# ESP07_Breakout.net
KiCad netlist of a schematic drawn in EAGLE
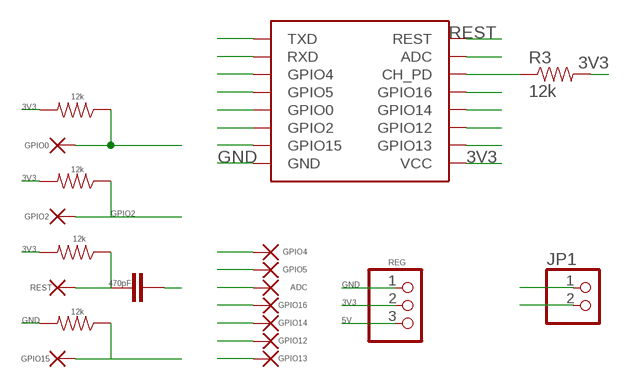
[diagram p0: schematic, sheet 1]

(export (version "E")
  (design (tool "Eeschema 10.0.6"))
  (components
    (comp (ref "ADC")
      (value "1,6/0,8")
      (footprint "eagle-import:1,6_0,8")
      (libsource (lib "eagle-import") (part "1,6/0,8"))
    )
    (comp (ref "C1")
      (value "470pF")
      (footprint "eagle-import:0603-CAP")
      (libsource (lib "eagle-import") (part "CAP0603-CAP"))
    )
    (comp (ref "GPIO0")
      (value "1,6/0,8")
      (footprint "eagle-import:1,6_0,8")
      (libsource (lib "eagle-import") (part "1,6/0,8"))
    )
    (comp (ref "GPIO2")
      (value "1,6/0,8")
      (footprint "eagle-import:1,6_0,8")
      (libsource (lib "eagle-import") (part "1,6/0,8"))
    )
    (comp (ref "GPIO4")
      (value "1,6/0,8")
      (footprint "eagle-import:1,6_0,8")
      (libsource (lib "eagle-import") (part "1,6/0,8"))
    )
    (comp (ref "GPIO5")
      (value "1,6/0,8")
      (footprint "eagle-import:1,6_0,8")
      (libsource (lib "eagle-import") (part "1,6/0,8"))
    )
    (comp (ref "GPIO12")
      (value "1,6/0,8")
      (footprint "eagle-import:1,6_0,8")
      (libsource (lib "eagle-import") (part "1,6/0,8"))
    )
    (comp (ref "GPIO13")
      (value "1,6/0,8")
      (footprint "eagle-import:1,6_0,8")
      (libsource (lib "eagle-import") (part "1,6/0,8"))
    )
    (comp (ref "GPIO14")
      (value "1,6/0,8")
      (footprint "eagle-import:1,6_0,8")
      (libsource (lib "eagle-import") (part "1,6/0,8"))
    )
    (comp (ref "GPIO15")
      (value "1,6/0,8")
      (footprint "eagle-import:1,6_0,8")
      (libsource (lib "eagle-import") (part "1,6/0,8"))
    )
    (comp (ref "GPIO16")
      (value "1,6/0,8")
      (footprint "eagle-import:1,6_0,8")
      (libsource (lib "eagle-import") (part "1,6/0,8"))
    )
    (comp (ref "JP1")
      (value "PINHD-1X2/90")
      (footprint "eagle-import:1X02_90")
      (libsource (lib "eagle-import") (part "PINHD-1X2/90"))
    )
    (comp (ref "R1")
      (value "12k")
      (footprint "eagle-import:0603-RES")
      (libsource (lib "eagle-import") (part "RESISTOR0603-RES"))
    )
    (comp (ref "R2")
      (value "12k")
      (footprint "eagle-import:0603-RES")
      (libsource (lib "eagle-import") (part "RESISTOR0603-RES"))
    )
    (comp (ref "R3")
      (value "12k")
      (footprint "eagle-import:0603-RES")
      (libsource (lib "eagle-import") (part "RESISTOR0603-RES"))
    )
    (comp (ref "R4")
      (value "12k")
      (footprint "eagle-import:0603-RES")
      (libsource (lib "eagle-import") (part "RESISTOR0603-RES"))
    )
    (comp (ref "R5")
      (value "12k")
      (footprint "eagle-import:0603-RES")
      (libsource (lib "eagle-import") (part "RESISTOR0603-RES"))
    )
    (comp (ref "REG")
      (value "PINHD-1X3")
      (footprint "eagle-import:1X03")
      (libsource (lib "eagle-import") (part "PINHD-1X3"))
    )
    (comp (ref "REST")
      (value "1,6/0,8")
      (footprint "eagle-import:1,6_0,8")
      (libsource (lib "eagle-import") (part "1,6/0,8"))
    )
    (comp (ref "U$1")
      (value "ESP-07")
      (footprint "eagle-import:ESP-07")
      (libsource (lib "eagle-import") (part "ESP-07"))
    )
  )
  (nets
    (net (code "1") (name "/3V3") (class "Default")
      (node (ref "R1") (pin "2") (pinfunction "2_2") (pintype "passive"))
      (node (ref "R2") (pin "2") (pinfunction "2_2") (pintype "passive"))
      (node (ref "R3") (pin "2") (pinfunction "2_2") (pintype "passive"))
      (node (ref "R4") (pin "2") (pinfunction "2_2") (pintype "passive"))
      (node (ref "REG") (pin "2") (pinfunction "2_2") (pintype "passive"))
      (node (ref "U$1") (pin "VCC") (pinfunction "VCC_VCC") (pintype "bidirectional"))
    )
    (net (code "2") (name "/5V") (class "Default")
      (node (ref "JP1") (pin "1") (pinfunction "1_1") (pintype "passive"))
      (node (ref "REG") (pin "3") (pinfunction "3_3") (pintype "passive"))
    )
    (net (code "3") (name "/ADC") (class "Default")
      (node (ref "ADC") (pin "1") (pinfunction "P_1") (pintype "passive"))
      (node (ref "U$1") (pin "ADC") (pinfunction "ADC_ADC") (pintype "bidirectional"))
    )
    (net (code "4") (name "/GND") (class "Default")
      (node (ref "C1") (pin "2") (pinfunction "2_2") (pintype "passive"))
      (node (ref "JP1") (pin "2") (pinfunction "2_2") (pintype "passive"))
      (node (ref "R5") (pin "2") (pinfunction "2_2") (pintype "passive"))
      (node (ref "REG") (pin "1") (pinfunction "1_1") (pintype "passive"))
      (node (ref "U$1") (pin "GND") (pinfunction "GND_GND") (pintype "bidirectional"))
    )
    (net (code "5") (name "/GPIO0") (class "Default")
      (node (ref "GPIO0") (pin "1") (pinfunction "P_1") (pintype "passive"))
      (node (ref "R1") (pin "1") (pinfunction "1_1") (pintype "passive"))
      (node (ref "U$1") (pin "GPIO00") (pinfunction "GPIO0_GPIO00") (pintype "bidirectional"))
    )
    (net (code "6") (name "/GPIO2") (class "Default")
      (node (ref "GPIO2") (pin "1") (pinfunction "P_1") (pintype "passive"))
      (node (ref "R2") (pin "1") (pinfunction "1_1") (pintype "passive"))
      (node (ref "U$1") (pin "GPIO2") (pinfunction "GPIO2_GPIO2") (pintype "bidirectional"))
    )
    (net (code "7") (name "/GPIO4") (class "Default")
      (node (ref "GPIO4") (pin "1") (pinfunction "P_1") (pintype "passive"))
      (node (ref "U$1") (pin "GPIO4") (pinfunction "GPIO4_GPIO4") (pintype "bidirectional"))
    )
    (net (code "8") (name "/GPIO5") (class "Default")
      (node (ref "GPIO5") (pin "1") (pinfunction "P_1") (pintype "passive"))
      (node (ref "U$1") (pin "GPIO5") (pinfunction "GPIO5_GPIO5") (pintype "bidirectional"))
    )
    (net (code "9") (name "/GPIO12") (class "Default")
      (node (ref "GPIO12") (pin "1") (pinfunction "P_1") (pintype "passive"))
      (node (ref "U$1") (pin "GPIO12") (pinfunction "GPIO12_GPIO12") (pintype "bidirectional"))
    )
    (net (code "10") (name "/GPIO13") (class "Default")
      (node (ref "GPIO13") (pin "1") (pinfunction "P_1") (pintype "passive"))
      (node (ref "U$1") (pin "GPIO13") (pinfunction "GPIO13_GPIO13") (pintype "bidirectional"))
    )
    (net (code "11") (name "/GPIO14") (class "Default")
      (node (ref "GPIO14") (pin "1") (pinfunction "P_1") (pintype "passive"))
      (node (ref "U$1") (pin "GPIO14") (pinfunction "GPIO14_GPIO14") (pintype "bidirectional"))
    )
    (net (code "12") (name "/GPIO15") (class "Default")
      (node (ref "GPIO15") (pin "1") (pinfunction "P_1") (pintype "passive"))
      (node (ref "R5") (pin "1") (pinfunction "1_1") (pintype "passive"))
      (node (ref "U$1") (pin "GPIO15") (pinfunction "GPIO15_GPIO15") (pintype "bidirectional"))
    )
    (net (code "13") (name "/GPIO16") (class "Default")
      (node (ref "GPIO16") (pin "1") (pinfunction "P_1") (pintype "passive"))
      (node (ref "U$1") (pin "GPIO16") (pinfunction "GPIO16_GPIO16") (pintype "bidirectional"))
    )
    (net (code "14") (name "/REST") (class "Default")
      (node (ref "C1") (pin "1") (pinfunction "1_1") (pintype "passive"))
      (node (ref "R4") (pin "1") (pinfunction "1_1") (pintype "passive"))
      (node (ref "REST") (pin "1") (pinfunction "P_1") (pintype "passive"))
      (node (ref "U$1") (pin "REST") (pinfunction "REST_REST") (pintype "bidirectional"))
    )
    (net (code "15") (name "Net-(R3-Pad1)") (class "Default")
      (node (ref "R3") (pin "1") (pinfunction "1_1") (pintype "passive"))
      (node (ref "U$1") (pin "CH_PD") (pinfunction "CH_PD_CH_PD") (pintype "bidirectional"))
    )
    (net (code "16") (name "unconnected-(U$1-PadRXD)") (class "Default")
      (node (ref "U$1") (pin "RXD") (pinfunction "RXD_RXD") (pintype "bidirectional"))
    )
    (net (code "17") (name "unconnected-(U$1-PadTXD)") (class "Default")
      (node (ref "U$1") (pin "TXD") (pinfunction "TXD_TXD") (pintype "bidirectional"))
    )
  )
)
